# ADCs.net
KiCad netlist of a schematic drawn in Altium Designer
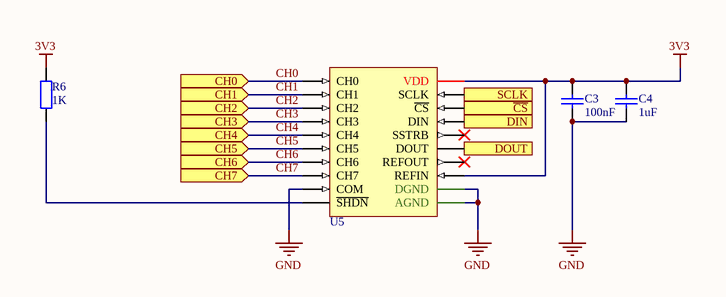
[diagram p0: ADCs.SchDoc]

(export (version "E")
  (design (tool "Eeschema 10.0.6"))
  (components
    (comp (ref "C3")
      (value "100nF")
      (footprint "FP_0805_CAP_085")
      (description "Capacitor")
      (fields (field (name "TOLERANCE") "+80%/-20%") (field (name "VOLTAGE") "25V"))
      (libsource (lib "hallglib") (part "CAP 100nF"))
    )
    (comp (ref "C4")
      (value "1uF")
      (footprint "FP_0805_CAP_085")
      (description "Capacitor")
      (fields (field (name "TOLERANCE") "+80%/-20%") (field (name "VOLTAGE") "25V"))
      (libsource (lib "hallglib") (part "CAP 1uF"))
    )
    (comp (ref "R6")
      (value "1K")
      (footprint "FP_0805_RES")
      (description "Resistor")
      (fields (field (name "TOLERANCE") "5%") (field (name "POWER") "125mW"))
      (libsource (lib "hallglib") (part "RES 1K"))
    )
    (comp (ref "U5")
      (value "MAX1110CAP+")
      (footprint "20-Pin SSOP")
      (description "Analogue to Digital Converter, Low Power, 8 bit, 50 kSPS, Single, 2.7 V, 5.5 V, SSOP")
      (libsource (lib "RobonAUT") (part "MAX1110CAP+"))
    )
  )
  (nets
    (net (code "1") (name "/CH0") (class "Default")
      (node (ref "U5") (pin "1") (pinfunction "CH0_1") (pintype "input"))
    )
    (net (code "2") (name "/CH1") (class "Default")
      (node (ref "U5") (pin "2") (pinfunction "CH1_2") (pintype "input"))
    )
    (net (code "3") (name "/CH2") (class "Default")
      (node (ref "U5") (pin "3") (pinfunction "CH2_3") (pintype "input"))
    )
    (net (code "4") (name "/CH3") (class "Default")
      (node (ref "U5") (pin "4") (pinfunction "CH3_4") (pintype "input"))
    )
    (net (code "5") (name "/CH4") (class "Default")
      (node (ref "U5") (pin "5") (pinfunction "CH4_5") (pintype "input"))
    )
    (net (code "6") (name "/CH5") (class "Default")
      (node (ref "U5") (pin "6") (pinfunction "CH5_6") (pintype "input"))
    )
    (net (code "7") (name "/CH6") (class "Default")
      (node (ref "U5") (pin "7") (pinfunction "CH6_7") (pintype "input"))
    )
    (net (code "8") (name "/CH7") (class "Default")
      (node (ref "U5") (pin "8") (pinfunction "CH7_8") (pintype "input"))
    )
    (net (code "9") (name "/DIN") (class "Default")
      (node (ref "U5") (pin "17") (pinfunction "DIN_17") (pintype "input"))
    )
    (net (code "10") (name "/DOUT") (class "Default")
      (node (ref "U5") (pin "15") (pinfunction "DOUT_15") (pintype "tri_state"))
    )
    (net (code "11") (name "/SCLK") (class "Default")
      (node (ref "U5") (pin "19") (pinfunction "SCLK_19") (pintype "input"))
    )
    (net (code "12") (name "/~{CS}") (class "Default")
      (node (ref "U5") (pin "18") (pinfunction "~{CS}_18") (pintype "input"))
    )
    (net (code "13") (name "3V3") (class "Default")
      (node (ref "C3") (pin "2") (pinfunction "2_2") (pintype "passive"))
      (node (ref "C4") (pin "2") (pinfunction "2_2") (pintype "passive"))
      (node (ref "R6") (pin "2") (pinfunction "2_2") (pintype "passive"))
      (node (ref "U5") (pin "11") (pinfunction "REFIN_11") (pintype "input"))
      (node (ref "U5") (pin "20") (pinfunction "VDD_20") (pintype "power_in"))
    )
    (net (code "14") (name "GND") (class "Default")
      (node (ref "C3") (pin "1") (pinfunction "1_1") (pintype "passive"))
      (node (ref "C4") (pin "1") (pinfunction "1_1") (pintype "passive"))
      (node (ref "U5") (pin "13") (pinfunction "AGND_13") (pintype "power_in"))
      (node (ref "U5") (pin "14") (pinfunction "DGND_14") (pintype "power_in"))
      (node (ref "U5") (pin "9") (pinfunction "COM_9") (pintype "input"))
    )
    (net (code "15") (name "Net-(U5-~{SHDN})") (class "Default")
      (node (ref "R6") (pin "1") (pinfunction "1_1") (pintype "passive"))
      (node (ref "U5") (pin "10") (pinfunction "~{SHDN}_10") (pintype "tri_state"))
    )
    (net (code "16") (name "unconnected-(U5-REFOUT-Pad12)") (class "Default")
      (node (ref "U5") (pin "12") (pinfunction "REFOUT_12") (pintype "output+no_connect"))
    )
    (net (code "17") (name "unconnected-(U5-SSTRB-Pad16)") (class "Default")
      (node (ref "U5") (pin "16") (pinfunction "SSTRB_16") (pintype "output+no_connect"))
    )
  )
)
